# USB_TO_UART.net
KiCad netlist of a schematic drawn in Altium Designer
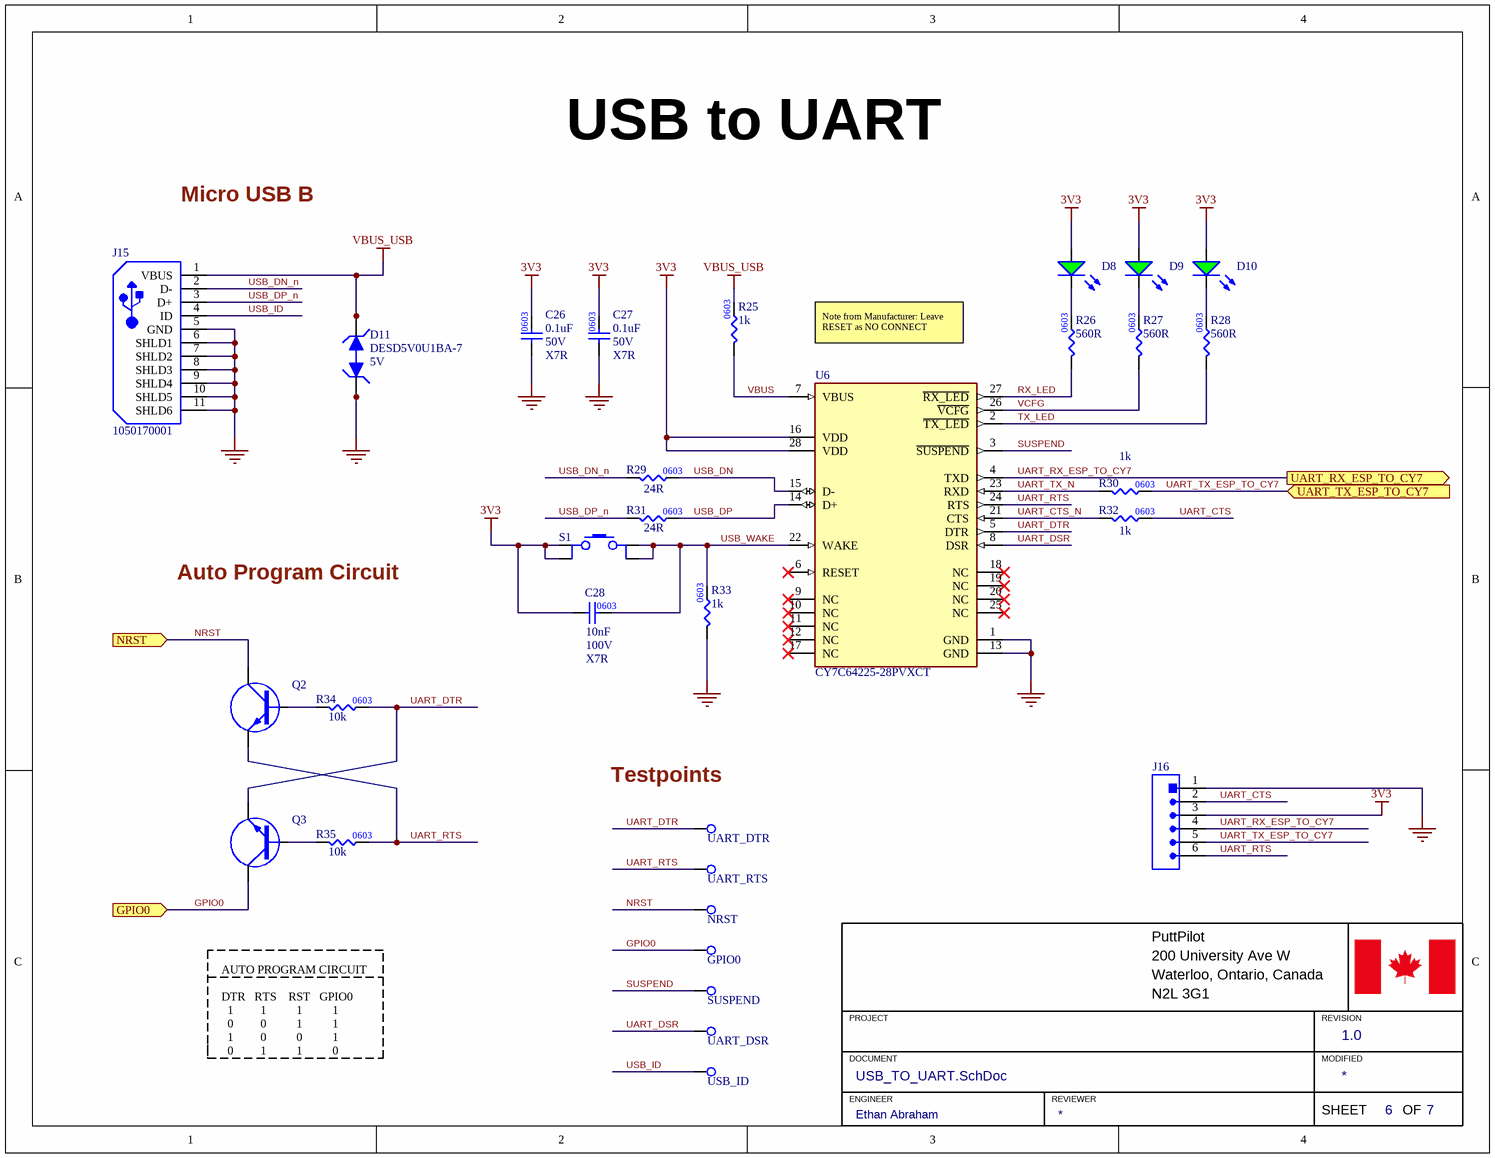
[diagram p0: USB_TO_UART.SchDoc]

(export (version "E")
  (design (tool "Eeschema 10.0.6"))
  (components
    (comp (ref "C26")
      (value "GCJ188R71H104KA12D")
      (footprint ".CAP_0603")
      (description "CAP CER 0.1uF 50V X7R 0603")
      (fields
        (field (name "MANUFACTURER") "Murata")
        (field (name "TEMPERATURE CHARACTERISTICS CODE") "X7R")
        (field (name "RATED DC VOLTAGE (URDC)") "50V")
        (field (name "CAPACITANCE") "0.1uF")
      )
      (libsource (lib "PuttPilot") (part "GCJ188R71H104KA12D"))
    )
    (comp (ref "C27")
      (value "GCJ188R71H104KA12D")
      (footprint ".CAP_0603")
      (description "CAP CER 0.1uF 50V X7R 0603")
      (fields
        (field (name "MANUFACTURER") "Murata")
        (field (name "TEMPERATURE CHARACTERISTICS CODE") "X7R")
        (field (name "RATED DC VOLTAGE (URDC)") "50V")
        (field (name "CAPACITANCE") "0.1uF")
      )
      (libsource (lib "PuttPilot") (part "GCJ188R71H104KA12D"))
    )
    (comp (ref "C28")
      (value "GCM188R72A103KA37D")
      (footprint ".CAP_0603")
      (description "CAP CER 0.01uF 100V X7R")
      (fields
        (field (name "MANUFACTURER") "Murata")
        (field (name "TOLERANCE") "10%")
        (field (name "DIELECTRIC") "X7R")
        (field (name "VOLTAGE RATING") "100V")
        (field (name "CAPACITANCE") "10nF")
      )
      (libsource (lib "PuttPilot") (part "GCM188R72A103KA37D"))
    )
    (comp (ref "D8")
      (value "LTST-C191KGKT")
      (footprint ".LED_0603")
      (description "LED GREEN 2V 0603")
      (fields (field (name "MANUFACTURER") "Vishay Lite-On"))
      (libsource (lib "PuttPilot") (part "LTST-C191KGKT"))
    )
    (comp (ref "D9")
      (value "LTST-C191KGKT")
      (footprint ".LED_0603")
      (description "LED GREEN 2V 0603")
      (fields (field (name "MANUFACTURER") "Vishay Lite-On"))
      (libsource (lib "PuttPilot") (part "LTST-C191KGKT"))
    )
    (comp (ref "D10")
      (value "LTST-C191KGKT")
      (footprint ".LED_0603")
      (description "LED GREEN 2V 0603")
      (fields (field (name "MANUFACTURER") "Vishay Lite-On"))
      (libsource (lib "PuttPilot") (part "LTST-C191KGKT"))
    )
    (comp (ref "D11")
      (value "DESD5V0U1BA-7")
      (footprint "DESD5V0U1BA-7")
      (description "TVS DIODE 5VWM")
      (fields (field (name "MANUFACTURER") "Diodes") (field (name "REP PK REVERSE VOLTAGE-MAX") "5V"))
      (libsource (lib "PuttPilot") (part "DESD5V0U1BA-7"))
    )
    (comp (ref "GPIO0")
      (value "RCWCTE")
      (footprint "RCWCTE")
      (description "SMT Test Point")
      (fields (field (name "MANUFACTURER") "KOA Speer"))
      (libsource (lib "PuttPilot") (part "RCWCTE"))
    )
    (comp (ref "J15")
      (value "1050170001")
      (footprint "USB_MICRO_B")
      (description "CONN USB MICRO B R/A")
      (fields (field (name "MANUFACTURER") "Molex"))
      (libsource (lib "PuttPilot") (part "1050170001"))
    )
    (comp (ref "J16")
      (value "PRPC040SAAN-RC_POS6")
      (footprint "HEADER_6POS_2.54MM")
      (description "CONN HEADER VERT 6POS 2.54MM")
      (libsource (lib "PuttPilot") (part "PRPC040SAAN-RC_POS6"))
    )
    (comp (ref "NRST")
      (value "RCWCTE")
      (footprint "RCWCTE")
      (description "SMT Test Point")
      (fields (field (name "MANUFACTURER") "KOA Speer"))
      (libsource (lib "PuttPilot") (part "RCWCTE"))
    )
    (comp (ref "Q2")
      (value "MMBT2222A-7-F")
      (footprint ".SOT-23-3")
      (description "NPN BJT 40V 600mA SOT-23")
      (fields (field (name "MANUFACTURER") "Diodes"))
      (libsource (lib "") (part "MMBT2222A-7-F_1"))
    )
    (comp (ref "Q3")
      (value "MMBT2222A-7-F")
      (footprint ".SOT-23-3")
      (description "NPN BJT 40V 600mA SOT-23")
      (fields (field (name "MANUFACTURER") "Diodes"))
      (libsource (lib "PuttPilot") (part "MMBT2222A-7-F"))
    )
    (comp (ref "R25")
      (value "RC0603FR-071KL")
      (footprint ".RES_0603")
      (description "RES 1K OHM 0603")
      (fields
        (field (name "MANUFACTURER") "Yageo")
        (field (name "TOLERANCE") "1%")
        (field (name "RESISTANCE") "1k")
      )
      (libsource (lib "PuttPilot") (part "RC0603FR-071KL"))
    )
    (comp (ref "R26")
      (value "RC0603FR-07560RL")
      (footprint ".RES_0603")
      (description "RES 560 OHM 0603")
      (fields
        (field (name "MANUFACTURER") "Yageo")
        (field (name "TOLERANCE") "1%")
        (field (name "RESISTANCE") "560R")
      )
      (libsource (lib "PuttPilot") (part "RC0603FR-07560RL"))
    )
    (comp (ref "R27")
      (value "RC0603FR-07560RL")
      (footprint ".RES_0603")
      (description "RES 560 OHM 0603")
      (fields
        (field (name "MANUFACTURER") "Yageo")
        (field (name "TOLERANCE") "1%")
        (field (name "RESISTANCE") "560R")
      )
      (libsource (lib "PuttPilot") (part "RC0603FR-07560RL"))
    )
    (comp (ref "R28")
      (value "RC0603FR-07560RL")
      (footprint ".RES_0603")
      (description "RES 560 OHM 0603")
      (fields
        (field (name "MANUFACTURER") "Yageo")
        (field (name "TOLERANCE") "1%")
        (field (name "RESISTANCE") "560R")
      )
      (libsource (lib "PuttPilot") (part "RC0603FR-07560RL"))
    )
    (comp (ref "R29")
      (value "RC0603FR-0724RL")
      (footprint ".RES_0603")
      (description "RES 24 OHM 0603")
      (fields
        (field (name "MANUFACTURER") "Yageo")
        (field (name "TOLERANCE") "1%")
        (field (name "RESISTANCE") "24R")
      )
      (libsource (lib "PuttPilot") (part "RC0603FR-0724RL"))
    )
    (comp (ref "R30")
      (value "RC0603FR-071KL")
      (footprint ".RES_0603")
      (description "RES 1K OHM 0603")
      (fields
        (field (name "MANUFACTURER") "Yageo")
        (field (name "TOLERANCE") "1%")
        (field (name "RESISTANCE") "1k")
      )
      (libsource (lib "PuttPilot") (part "RC0603FR-071KL"))
    )
    (comp (ref "R31")
      (value "RC0603FR-0724RL")
      (footprint ".RES_0603")
      (description "RES 24 OHM 0603")
      (fields
        (field (name "MANUFACTURER") "Yageo")
        (field (name "TOLERANCE") "1%")
        (field (name "RESISTANCE") "24R")
      )
      (libsource (lib "PuttPilot") (part "RC0603FR-0724RL"))
    )
    (comp (ref "R32")
      (value "RC0603FR-071KL")
      (footprint ".RES_0603")
      (description "RES 1K OHM 0603")
      (fields
        (field (name "MANUFACTURER") "Yageo")
        (field (name "TOLERANCE") "1%")
        (field (name "RESISTANCE") "1k")
      )
      (libsource (lib "PuttPilot") (part "RC0603FR-071KL"))
    )
    (comp (ref "R33")
      (value "RC0603FR-071KL")
      (footprint ".RES_0603")
      (description "RES 1K OHM 0603")
      (fields
        (field (name "MANUFACTURER") "Yageo")
        (field (name "TOLERANCE") "1%")
        (field (name "RESISTANCE") "1k")
      )
      (libsource (lib "PuttPilot") (part "RC0603FR-071KL"))
    )
    (comp (ref "R34")
      (value "RC0603FR-0710KL")
      (footprint ".RES_0603")
      (description "RES 10K OHM 0603")
      (fields
        (field (name "MANUFACTURER") "Yageo")
        (field (name "TOLERANCE") "1%")
        (field (name "RESISTANCE") "10k")
      )
      (libsource (lib "PuttPilot") (part "RC0603FR-0710KL"))
    )
    (comp (ref "R35")
      (value "RC0603FR-0710KL")
      (footprint ".RES_0603")
      (description "RES 10K OHM 0603")
      (fields
        (field (name "MANUFACTURER") "Yageo")
        (field (name "TOLERANCE") "1%")
        (field (name "RESISTANCE") "10k")
      )
      (libsource (lib "PuttPilot") (part "RC0603FR-0710KL"))
    )
    (comp (ref "S1")
      (value "PTS647SN38SMTR2LFS")
      (footprint "PTS647SN38SMTR2LFS")
      (description "SWITCH TACTILE SPST-NO 0.05A 12V")
      (fields (field (name "MANUFACTURER") "ITT C&K"))
      (libsource (lib "PuttPilot") (part "PTS647SN38SMTR2LFS"))
    )
    (comp (ref "SUSPEND")
      (value "RCWCTE")
      (footprint "RCWCTE")
      (description "SMT Test Point")
      (fields (field (name "MANUFACTURER") "KOA Speer"))
      (libsource (lib "PuttPilot") (part "RCWCTE"))
    )
    (comp (ref "U6")
      (value "CY7C64225-28PVXCT")
      (footprint "CY7C64225-28PVXCT")
      (description "USB to UART SOP 28 Pin")
      (fields (field (name "MANUFACTURER") "Infineon"))
      (libsource (lib "PuttPilot") (part "CY7C64225-28PVXCT"))
    )
    (comp (ref "UART_DSR")
      (value "RCWCTE")
      (footprint "RCWCTE")
      (description "SMT Test Point")
      (fields (field (name "MANUFACTURER") "KOA Speer"))
      (libsource (lib "PuttPilot") (part "RCWCTE"))
    )
    (comp (ref "UART_DTR")
      (value "RCWCTE")
      (footprint "RCWCTE")
      (description "SMT Test Point")
      (fields (field (name "MANUFACTURER") "KOA Speer"))
      (libsource (lib "PuttPilot") (part "RCWCTE"))
    )
    (comp (ref "UART_RTS")
      (value "RCWCTE")
      (footprint "RCWCTE")
      (description "SMT Test Point")
      (fields (field (name "MANUFACTURER") "KOA Speer"))
      (libsource (lib "PuttPilot") (part "RCWCTE"))
    )
    (comp (ref "USB_ID")
      (value "RCWCTE")
      (footprint "RCWCTE")
      (description "SMT Test Point")
      (fields (field (name "MANUFACTURER") "KOA Speer"))
      (libsource (lib "PuttPilot") (part "RCWCTE"))
    )
  )
  (nets
    (net (code "1") (name "/GPIO0") (class "Default")
      (node (ref "GPIO0") (pin "1") (pinfunction "1_1") (pintype "passive"))
      (node (ref "Q3") (pin "2") (pinfunction "Emitter_2") (pintype "passive"))
    )
    (net (code "2") (name "/NRST") (class "Default")
      (node (ref "NRST") (pin "1") (pinfunction "1_1") (pintype "passive"))
      (node (ref "Q2") (pin "2") (pinfunction "Emitter_2") (pintype "passive"))
    )
    (net (code "3") (name "/RX_LED") (class "Default")
      (node (ref "R26") (pin "1") (pinfunction "1_1") (pintype "passive"))
      (node (ref "U6") (pin "27") (pinfunction "~{RX_LED}_27") (pintype "output"))
    )
    (net (code "4") (name "/SUSPEND") (class "Default")
      (node (ref "SUSPEND") (pin "1") (pinfunction "1_1") (pintype "passive"))
      (node (ref "U6") (pin "3") (pinfunction "~{SUSPEND}_3") (pintype "output"))
    )
    (net (code "5") (name "/TX_LED") (class "Default")
      (node (ref "R28") (pin "1") (pinfunction "1_1") (pintype "passive"))
      (node (ref "U6") (pin "2") (pinfunction "~{TX_LED}_2") (pintype "output"))
    )
    (net (code "6") (name "/UART_CTS") (class "Default")
      (node (ref "J16") (pin "2") (pinfunction "2_2") (pintype "passive"))
      (node (ref "R32") (pin "2") (pinfunction "2_2") (pintype "passive"))
    )
    (net (code "7") (name "/UART_CTS_N") (class "Default")
      (node (ref "R32") (pin "1") (pinfunction "1_1") (pintype "passive"))
      (node (ref "U6") (pin "21") (pinfunction "CTS_21") (pintype "input"))
    )
    (net (code "8") (name "/UART_DSR") (class "Default")
      (node (ref "U6") (pin "8") (pinfunction "DSR_8") (pintype "input"))
      (node (ref "UART_DSR") (pin "1") (pinfunction "1_1") (pintype "passive"))
    )
    (net (code "9") (name "/UART_DTR") (class "Default")
      (node (ref "Q3") (pin "3") (pinfunction "Collector_3") (pintype "passive"))
      (node (ref "R34") (pin "2") (pinfunction "2_2") (pintype "passive"))
      (node (ref "U6") (pin "5") (pinfunction "DTR_5") (pintype "output"))
      (node (ref "UART_DTR") (pin "1") (pinfunction "1_1") (pintype "passive"))
    )
    (net (code "10") (name "/UART_RTS") (class "Default")
      (node (ref "J16") (pin "6") (pinfunction "6_6") (pintype "passive"))
      (node (ref "Q2") (pin "3") (pinfunction "Collector_3") (pintype "passive"))
      (node (ref "R35") (pin "2") (pinfunction "2_2") (pintype "passive"))
      (node (ref "U6") (pin "24") (pinfunction "RTS_24") (pintype "output"))
      (node (ref "UART_RTS") (pin "1") (pinfunction "1_1") (pintype "passive"))
    )
    (net (code "11") (name "/UART_RX_ESP_TO_CY7") (class "Default")
      (node (ref "J16") (pin "4") (pinfunction "4_4") (pintype "passive"))
      (node (ref "U6") (pin "4") (pinfunction "TXD_4") (pintype "output"))
    )
    (net (code "12") (name "/UART_TX_ESP_TO_CY7") (class "Default")
      (node (ref "J16") (pin "5") (pinfunction "5_5") (pintype "passive"))
      (node (ref "R30") (pin "2") (pinfunction "2_2") (pintype "passive"))
    )
    (net (code "13") (name "/UART_TX_N") (class "Default")
      (node (ref "R30") (pin "1") (pinfunction "1_1") (pintype "passive"))
      (node (ref "U6") (pin "23") (pinfunction "RXD_23") (pintype "input"))
    )
    (net (code "14") (name "/USB_DN") (class "Default")
      (node (ref "R29") (pin "2") (pinfunction "2_2") (pintype "passive"))
      (node (ref "U6") (pin "15") (pinfunction "D-_15") (pintype "bidirectional"))
    )
    (net (code "15") (name "/USB_DN_n") (class "Default")
      (node (ref "J15") (pin "2") (pinfunction "D-_2") (pintype "passive"))
      (node (ref "R29") (pin "1") (pinfunction "1_1") (pintype "passive"))
    )
    (net (code "16") (name "/USB_DP") (class "Default")
      (node (ref "R31") (pin "2") (pinfunction "2_2") (pintype "passive"))
      (node (ref "U6") (pin "14") (pinfunction "D+_14") (pintype "bidirectional"))
    )
    (net (code "17") (name "/USB_DP_n") (class "Default")
      (node (ref "J15") (pin "3") (pinfunction "D+_3") (pintype "passive"))
      (node (ref "R31") (pin "1") (pinfunction "1_1") (pintype "passive"))
    )
    (net (code "18") (name "/USB_ID") (class "Default")
      (node (ref "J15") (pin "4") (pinfunction "ID_4") (pintype "passive"))
      (node (ref "USB_ID") (pin "1") (pinfunction "1_1") (pintype "passive"))
    )
    (net (code "19") (name "/USB_WAKE") (class "Default")
      (node (ref "C28") (pin "2") (pinfunction "2_2") (pintype "passive"))
      (node (ref "R33") (pin "2") (pinfunction "2_2") (pintype "passive"))
      (node (ref "S1") (pin "3") (pinfunction "3_3") (pintype "passive"))
      (node (ref "S1") (pin "4") (pinfunction "4_4") (pintype "passive"))
      (node (ref "U6") (pin "22") (pinfunction "WAKE_22") (pintype "input"))
    )
    (net (code "20") (name "/VBUS") (class "Default")
      (node (ref "R25") (pin "1") (pinfunction "1_1") (pintype "passive"))
      (node (ref "U6") (pin "7") (pinfunction "VBUS_7") (pintype "input"))
    )
    (net (code "21") (name "/VCFG") (class "Default")
      (node (ref "R27") (pin "1") (pinfunction "1_1") (pintype "passive"))
      (node (ref "U6") (pin "26") (pinfunction "~{VCFG}_26") (pintype "output"))
    )
    (net (code "22") (name "3V3") (class "Default")
      (node (ref "C26") (pin "2") (pinfunction "2_2") (pintype "passive"))
      (node (ref "C27") (pin "2") (pinfunction "2_2") (pintype "passive"))
      (node (ref "C28") (pin "1") (pinfunction "1_1") (pintype "passive"))
      (node (ref "D10") (pin "1") (pinfunction "A_1") (pintype "passive"))
      (node (ref "D8") (pin "1") (pinfunction "A_1") (pintype "passive"))
      (node (ref "D9") (pin "1") (pinfunction "A_1") (pintype "passive"))
      (node (ref "J16") (pin "3") (pinfunction "3_3") (pintype "passive"))
      (node (ref "S1") (pin "1") (pinfunction "1_1") (pintype "passive"))
      (node (ref "S1") (pin "2") (pinfunction "2_2") (pintype "passive"))
      (node (ref "U6") (pin "16") (pinfunction "VDD_16") (pintype "power_in"))
      (node (ref "U6") (pin "28") (pinfunction "VDD_28") (pintype "power_in"))
    )
    (net (code "23") (name "GND") (class "Default")
      (node (ref "C26") (pin "1") (pinfunction "1_1") (pintype "passive"))
      (node (ref "C27") (pin "1") (pinfunction "1_1") (pintype "passive"))
      (node (ref "D11") (pin "1") (pinfunction "Pin_1_1") (pintype "passive"))
      (node (ref "J15") (pin "10") (pinfunction "SHLD5_10") (pintype "passive"))
      (node (ref "J15") (pin "11") (pinfunction "SHLD6_11") (pintype "passive"))
      (node (ref "J15") (pin "5") (pinfunction "GND_5") (pintype "passive"))
      (node (ref "J15") (pin "6") (pinfunction "SHLD1_6") (pintype "passive"))
      (node (ref "J15") (pin "7") (pinfunction "SHLD2_7") (pintype "passive"))
      (node (ref "J15") (pin "8") (pinfunction "SHLD3_8") (pintype "passive"))
      (node (ref "J15") (pin "9") (pinfunction "SHLD4_9") (pintype "passive"))
      (node (ref "J16") (pin "1") (pinfunction "1_1") (pintype "passive"))
      (node (ref "R33") (pin "1") (pinfunction "1_1") (pintype "passive"))
      (node (ref "U6") (pin "1") (pinfunction "GND_1") (pintype "power_in"))
      (node (ref "U6") (pin "13") (pinfunction "GND_13") (pintype "power_in"))
    )
    (net (code "24") (name "Net-(D8-K)") (class "Default")
      (node (ref "D8") (pin "2") (pinfunction "K_2") (pintype "passive"))
      (node (ref "R26") (pin "2") (pinfunction "2_2") (pintype "passive"))
    )
    (net (code "25") (name "Net-(D9-K)") (class "Default")
      (node (ref "D9") (pin "2") (pinfunction "K_2") (pintype "passive"))
      (node (ref "R27") (pin "2") (pinfunction "2_2") (pintype "passive"))
    )
    (net (code "26") (name "Net-(D10-K)") (class "Default")
      (node (ref "D10") (pin "2") (pinfunction "K_2") (pintype "passive"))
      (node (ref "R28") (pin "2") (pinfunction "2_2") (pintype "passive"))
    )
    (net (code "27") (name "Net-(Q2-Base)") (class "Default")
      (node (ref "Q2") (pin "1") (pinfunction "Base_1") (pintype "passive"))
      (node (ref "R34") (pin "1") (pinfunction "1_1") (pintype "passive"))
    )
    (net (code "28") (name "Net-(Q3-Base)") (class "Default")
      (node (ref "Q3") (pin "1") (pinfunction "Base_1") (pintype "passive"))
      (node (ref "R35") (pin "1") (pinfunction "1_1") (pintype "passive"))
    )
    (net (code "29") (name "VBUS_USB") (class "Default")
      (node (ref "D11") (pin "2") (pinfunction "Pin_2_2") (pintype "passive"))
      (node (ref "J15") (pin "1") (pinfunction "VBUS_1") (pintype "passive"))
      (node (ref "R25") (pin "2") (pinfunction "2_2") (pintype "passive"))
    )
    (net (code "30") (name "unconnected-(U6-NC-Pad9)") (class "Default")
      (node (ref "U6") (pin "9") (pinfunction "NC_9") (pintype "passive+no_connect"))
    )
    (net (code "31") (name "unconnected-(U6-NC-Pad10)") (class "Default")
      (node (ref "U6") (pin "10") (pinfunction "NC_10") (pintype "passive+no_connect"))
    )
    (net (code "32") (name "unconnected-(U6-NC-Pad11)") (class "Default")
      (node (ref "U6") (pin "11") (pinfunction "NC_11") (pintype "passive+no_connect"))
    )
    (net (code "33") (name "unconnected-(U6-NC-Pad12)") (class "Default")
      (node (ref "U6") (pin "12") (pinfunction "NC_12") (pintype "passive+no_connect"))
    )
    (net (code "34") (name "unconnected-(U6-NC-Pad17)") (class "Default")
      (node (ref "U6") (pin "17") (pinfunction "NC_17") (pintype "passive+no_connect"))
    )
    (net (code "35") (name "unconnected-(U6-NC-Pad18)") (class "Default")
      (node (ref "U6") (pin "18") (pinfunction "NC_18") (pintype "passive+no_connect"))
    )
    (net (code "36") (name "unconnected-(U6-NC-Pad19)") (class "Default")
      (node (ref "U6") (pin "19") (pinfunction "NC_19") (pintype "passive+no_connect"))
    )
    (net (code "37") (name "unconnected-(U6-NC-Pad20)") (class "Default")
      (node (ref "U6") (pin "20") (pinfunction "NC_20") (pintype "passive+no_connect"))
    )
    (net (code "38") (name "unconnected-(U6-NC-Pad25)") (class "Default")
      (node (ref "U6") (pin "25") (pinfunction "NC_25") (pintype "passive+no_connect"))
    )
    (net (code "39") (name "unconnected-(U6-RESET-Pad6)") (class "Default")
      (node (ref "U6") (pin "6") (pinfunction "RESET_6") (pintype "input+no_connect"))
    )
  )
)
